# water_level_indicator.net
KiCad netlist of a schematic drawn in EAGLE
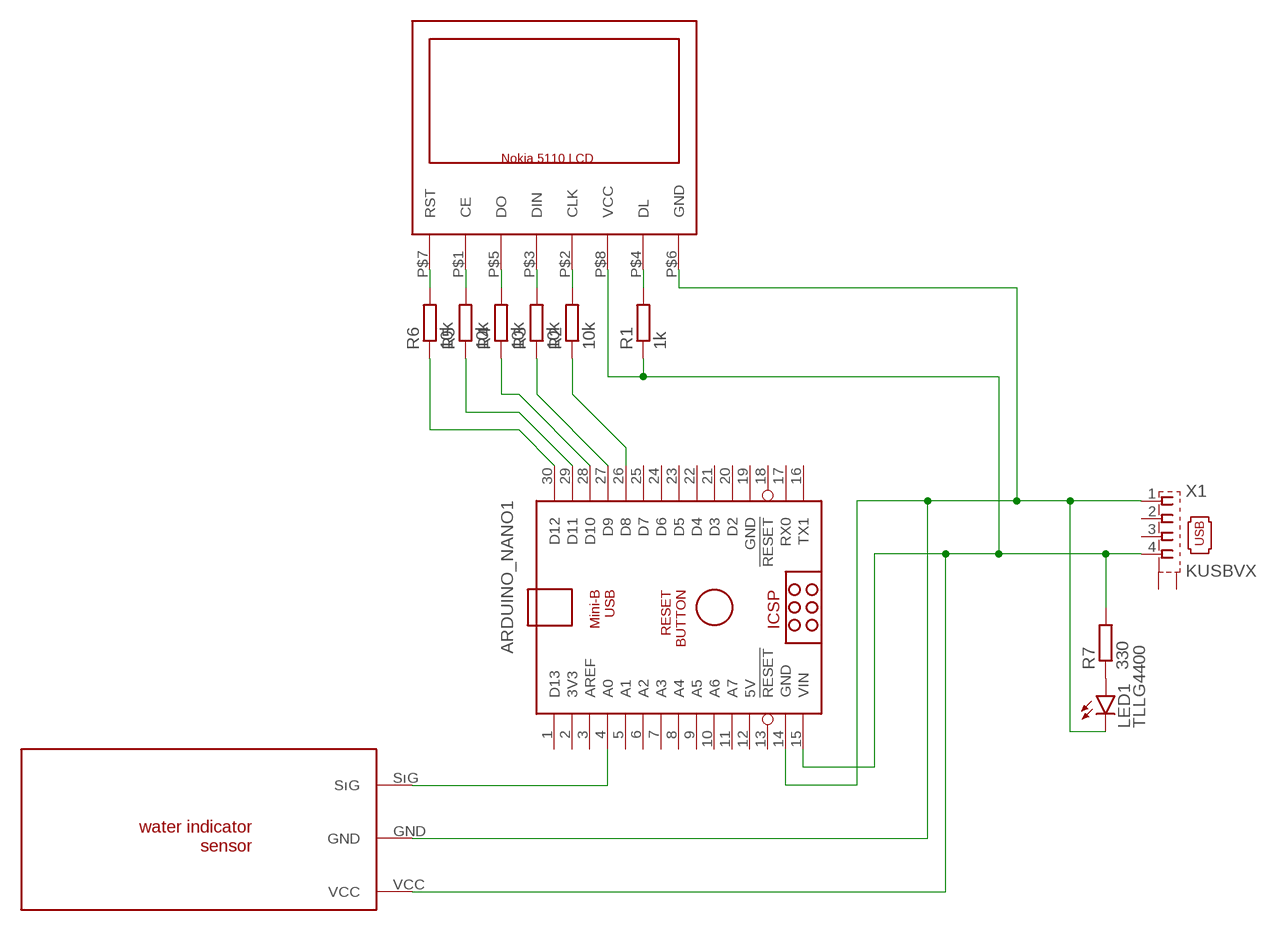
[diagram p0: schematic, sheet 1]

(export (version "E")
  (design (tool "Eeschema 10.0.6"))
  (components
    (comp (ref "ARDUINO_NANO1")
      (value "ARDUINO_NANO")
      (footprint "eagle-import:ARDUINO_NANO")
      (libsource (lib "eagle-import") (part "ARDUINO_NANO"))
    )
    (comp (ref "LED1")
      (value "TLLG4400")
      (footprint "eagle-import:LED3MM")
      (fields (field (name "MF") "VISHAY SEMICONDUCTOR"))
      (libsource (lib "eagle-import") (part "TLLG4400"))
    )
    (comp (ref "R1")
      (value "1k")
      (footprint "eagle-import:0207_10")
      (libsource (lib "eagle-import") (part "R-EU_0207/10"))
    )
    (comp (ref "R2")
      (value "10k")
      (footprint "eagle-import:0207_10")
      (libsource (lib "eagle-import") (part "R-EU_0207/10"))
    )
    (comp (ref "R3")
      (value "10k")
      (footprint "eagle-import:0207_10")
      (libsource (lib "eagle-import") (part "R-EU_0207/10"))
    )
    (comp (ref "R4")
      (value "10k")
      (footprint "eagle-import:0207_10")
      (libsource (lib "eagle-import") (part "R-EU_0207/10"))
    )
    (comp (ref "R5")
      (value "10k")
      (footprint "eagle-import:0207_10")
      (libsource (lib "eagle-import") (part "R-EU_0207/10"))
    )
    (comp (ref "R6")
      (value "10k")
      (footprint "eagle-import:0207_10")
      (libsource (lib "eagle-import") (part "R-EU_0207/10"))
    )
    (comp (ref "R7")
      (value "330")
      (footprint "eagle-import:0207_10")
      (libsource (lib "eagle-import") (part "R-EU_0207/10"))
    )
    (comp (ref "U$1")
      (value "WATER_LEVEL_IND")
      (footprint "eagle-import:WATER_LEVEL_IND")
      (libsource (lib "eagle-import") (part "WATER_LEVEL_IND"))
    )
    (comp (ref "U$2")
      (value "NOKİA5110LCD")
      (footprint "eagle-import:NOKİA5110LCD")
      (libsource (lib "eagle-import") (part "NOKİA5110LCD"))
    )
    (comp (ref "X1")
      (value "KUSBVX")
      (footprint "eagle-import:KUSBVX")
      (libsource (lib "eagle-import") (part "KUSBVX"))
    )
  )
  (nets
    (net (code "1") (name "/5V") (class "Default")
      (node (ref "ARDUINO_NANO1") (pin "12") (pinfunction "5V_12") (pintype "power_in"))
    )
    (net (code "2") (name "/GND") (class "Default")
      (node (ref "ARDUINO_NANO1") (pin "19") (pinfunction "GND_19") (pintype "power_in"))
    )
    (net (code "3") (name "Net-(ARDUINO_NANO1-A0)") (class "Default")
      (node (ref "ARDUINO_NANO1") (pin "4") (pinfunction "A0_4") (pintype "bidirectional"))
      (node (ref "U$1") (pin "SıG") (pinfunction "SıG_SıG") (pintype "bidirectional"))
    )
    (net (code "4") (name "Net-(ARDUINO_NANO1-D8)") (class "Default")
      (node (ref "ARDUINO_NANO1") (pin "26") (pinfunction "D8_26") (pintype "bidirectional"))
      (node (ref "R2") (pin "1") (pinfunction "1_1") (pintype "passive"))
    )
    (net (code "5") (name "Net-(ARDUINO_NANO1-D9)") (class "Default")
      (node (ref "ARDUINO_NANO1") (pin "27") (pinfunction "D9_27") (pintype "bidirectional"))
      (node (ref "R3") (pin "1") (pinfunction "1_1") (pintype "passive"))
    )
    (net (code "6") (name "Net-(ARDUINO_NANO1-D10)") (class "Default")
      (node (ref "ARDUINO_NANO1") (pin "28") (pinfunction "D10_28") (pintype "bidirectional"))
      (node (ref "R4") (pin "1") (pinfunction "1_1") (pintype "passive"))
    )
    (net (code "7") (name "Net-(ARDUINO_NANO1-D11)") (class "Default")
      (node (ref "ARDUINO_NANO1") (pin "29") (pinfunction "D11_29") (pintype "bidirectional"))
      (node (ref "R5") (pin "1") (pinfunction "1_1") (pintype "passive"))
    )
    (net (code "8") (name "Net-(ARDUINO_NANO1-D12)") (class "Default")
      (node (ref "ARDUINO_NANO1") (pin "30") (pinfunction "D12_30") (pintype "bidirectional"))
      (node (ref "R6") (pin "1") (pinfunction "1_1") (pintype "passive"))
    )
    (net (code "9") (name "Net-(ARDUINO_NANO1-VIN)") (class "Default")
      (node (ref "ARDUINO_NANO1") (pin "15") (pinfunction "VIN_15") (pintype "power_in"))
      (node (ref "R1") (pin "1") (pinfunction "1_1") (pintype "passive"))
      (node (ref "R7") (pin "2") (pinfunction "2_2") (pintype "passive"))
      (node (ref "U$1") (pin "VCC") (pinfunction "VCC_VCC") (pintype "bidirectional"))
      (node (ref "U$2") (pin "P$8") (pinfunction "VCC_P$8") (pintype "bidirectional"))
      (node (ref "X1") (pin "4") (pinfunction "4_4") (pintype "passive"))
    )
    (net (code "10") (name "Net-(LED1-C)") (class "Default")
      (node (ref "ARDUINO_NANO1") (pin "14") (pinfunction "GND_14") (pintype "power_in"))
      (node (ref "LED1") (pin "K") (pinfunction "C_K") (pintype "passive"))
      (node (ref "U$1") (pin "GND") (pinfunction "GND_GND") (pintype "bidirectional"))
      (node (ref "U$2") (pin "P$6") (pinfunction "GND_P$6") (pintype "bidirectional"))
      (node (ref "X1") (pin "1") (pinfunction "1_1") (pintype "passive"))
    )
    (net (code "11") (name "Net-(LED1-PadA)") (class "Default")
      (node (ref "LED1") (pin "A") (pinfunction "A_A") (pintype "passive"))
      (node (ref "R7") (pin "1") (pinfunction "1_1") (pintype "passive"))
    )
    (net (code "12") (name "Net-(U$2-CE)") (class "Default")
      (node (ref "R5") (pin "2") (pinfunction "2_2") (pintype "passive"))
      (node (ref "U$2") (pin "P$1") (pinfunction "CE_P$1") (pintype "bidirectional"))
    )
    (net (code "13") (name "Net-(U$2-CLK)") (class "Default")
      (node (ref "R2") (pin "2") (pinfunction "2_2") (pintype "passive"))
      (node (ref "U$2") (pin "P$2") (pinfunction "CLK_P$2") (pintype "bidirectional"))
    )
    (net (code "14") (name "Net-(U$2-DIN)") (class "Default")
      (node (ref "R3") (pin "2") (pinfunction "2_2") (pintype "passive"))
      (node (ref "U$2") (pin "P$3") (pinfunction "DIN_P$3") (pintype "bidirectional"))
    )
    (net (code "15") (name "Net-(U$2-DL)") (class "Default")
      (node (ref "R1") (pin "2") (pinfunction "2_2") (pintype "passive"))
      (node (ref "U$2") (pin "P$4") (pinfunction "DL_P$4") (pintype "bidirectional"))
    )
    (net (code "16") (name "Net-(U$2-DO)") (class "Default")
      (node (ref "R4") (pin "2") (pinfunction "2_2") (pintype "passive"))
      (node (ref "U$2") (pin "P$5") (pinfunction "DO_P$5") (pintype "bidirectional"))
    )
    (net (code "17") (name "Net-(U$2-RST)") (class "Default")
      (node (ref "R6") (pin "2") (pinfunction "2_2") (pintype "passive"))
      (node (ref "U$2") (pin "P$7") (pinfunction "RST_P$7") (pintype "bidirectional"))
    )
    (net (code "18") (name "unconnected-(ARDUINO_NANO1-3V3-Pad2)") (class "Default")
      (node (ref "ARDUINO_NANO1") (pin "2") (pinfunction "3V3_2") (pintype "output"))
    )
    (net (code "19") (name "unconnected-(ARDUINO_NANO1-A1-Pad5)") (class "Default")
      (node (ref "ARDUINO_NANO1") (pin "5") (pinfunction "A1_5") (pintype "bidirectional"))
    )
    (net (code "20") (name "unconnected-(ARDUINO_NANO1-A2-Pad6)") (class "Default")
      (node (ref "ARDUINO_NANO1") (pin "6") (pinfunction "A2_6") (pintype "bidirectional"))
    )
    (net (code "21") (name "unconnected-(ARDUINO_NANO1-A3-Pad7)") (class "Default")
      (node (ref "ARDUINO_NANO1") (pin "7") (pinfunction "A3_7") (pintype "bidirectional"))
    )
    (net (code "22") (name "unconnected-(ARDUINO_NANO1-A4-Pad8)") (class "Default")
      (node (ref "ARDUINO_NANO1") (pin "8") (pinfunction "A4_8") (pintype "bidirectional"))
    )
    (net (code "23") (name "unconnected-(ARDUINO_NANO1-A5-Pad9)") (class "Default")
      (node (ref "ARDUINO_NANO1") (pin "9") (pinfunction "A5_9") (pintype "bidirectional"))
    )
    (net (code "24") (name "unconnected-(ARDUINO_NANO1-A6-Pad10)") (class "Default")
      (node (ref "ARDUINO_NANO1") (pin "10") (pinfunction "A6_10") (pintype "bidirectional"))
    )
    (net (code "25") (name "unconnected-(ARDUINO_NANO1-A7-Pad11)") (class "Default")
      (node (ref "ARDUINO_NANO1") (pin "11") (pinfunction "A7_11") (pintype "bidirectional"))
    )
    (net (code "26") (name "unconnected-(ARDUINO_NANO1-AREF-Pad3)") (class "Default")
      (node (ref "ARDUINO_NANO1") (pin "3") (pinfunction "AREF_3") (pintype "input"))
    )
    (net (code "27") (name "unconnected-(ARDUINO_NANO1-D2-Pad20)") (class "Default")
      (node (ref "ARDUINO_NANO1") (pin "20") (pinfunction "D2_20") (pintype "bidirectional"))
    )
    (net (code "28") (name "unconnected-(ARDUINO_NANO1-D3-Pad21)") (class "Default")
      (node (ref "ARDUINO_NANO1") (pin "21") (pinfunction "D3_21") (pintype "bidirectional"))
    )
    (net (code "29") (name "unconnected-(ARDUINO_NANO1-D4-Pad22)") (class "Default")
      (node (ref "ARDUINO_NANO1") (pin "22") (pinfunction "D4_22") (pintype "bidirectional"))
    )
    (net (code "30") (name "unconnected-(ARDUINO_NANO1-D5-Pad23)") (class "Default")
      (node (ref "ARDUINO_NANO1") (pin "23") (pinfunction "D5_23") (pintype "bidirectional"))
    )
    (net (code "31") (name "unconnected-(ARDUINO_NANO1-D6-Pad24)") (class "Default")
      (node (ref "ARDUINO_NANO1") (pin "24") (pinfunction "D6_24") (pintype "bidirectional"))
    )
    (net (code "32") (name "unconnected-(ARDUINO_NANO1-D7-Pad25)") (class "Default")
      (node (ref "ARDUINO_NANO1") (pin "25") (pinfunction "D7_25") (pintype "bidirectional"))
    )
    (net (code "33") (name "unconnected-(ARDUINO_NANO1-D13-Pad1)") (class "Default")
      (node (ref "ARDUINO_NANO1") (pin "1") (pinfunction "D13_1") (pintype "bidirectional"))
    )
    (net (code "34") (name "unconnected-(ARDUINO_NANO1-RX0-Pad17)") (class "Default")
      (node (ref "ARDUINO_NANO1") (pin "17") (pinfunction "RX0_17") (pintype "bidirectional"))
    )
    (net (code "35") (name "unconnected-(ARDUINO_NANO1-TX1-Pad16)") (class "Default")
      (node (ref "ARDUINO_NANO1") (pin "16") (pinfunction "TX1_16") (pintype "bidirectional"))
    )
    (net (code "36") (name "unconnected-(ARDUINO_NANO1-~{RESET}-Pad13)") (class "Default")
      (node (ref "ARDUINO_NANO1") (pin "13") (pinfunction "~{RESET}_13") (pintype "input"))
    )
    (net (code "37") (name "unconnected-(ARDUINO_NANO1-~{RESET}-Pad18)") (class "Default")
      (node (ref "ARDUINO_NANO1") (pin "18") (pinfunction "~{RESET}_18") (pintype "input"))
    )
    (net (code "38") (name "unconnected-(X1-Pad2)") (class "Default")
      (node (ref "X1") (pin "2") (pinfunction "2_2") (pintype "passive"))
    )
    (net (code "39") (name "unconnected-(X1-Pad3)") (class "Default")
      (node (ref "X1") (pin "3") (pinfunction "3_3") (pintype "passive"))
    )
    (net (code "40") (name "unconnected-(X1-S1-PadM1)") (class "Default")
      (node (ref "X1") (pin "M1") (pinfunction "S1_M1") (pintype "passive"))
    )
    (net (code "41") (name "unconnected-(X1-S2-PadM2)") (class "Default")
      (node (ref "X1") (pin "M2") (pinfunction "S2_M2") (pintype "passive"))
    )
  )
)
